# CPU_STM32H7.net
KiCad netlist of a schematic drawn in Altium Designer
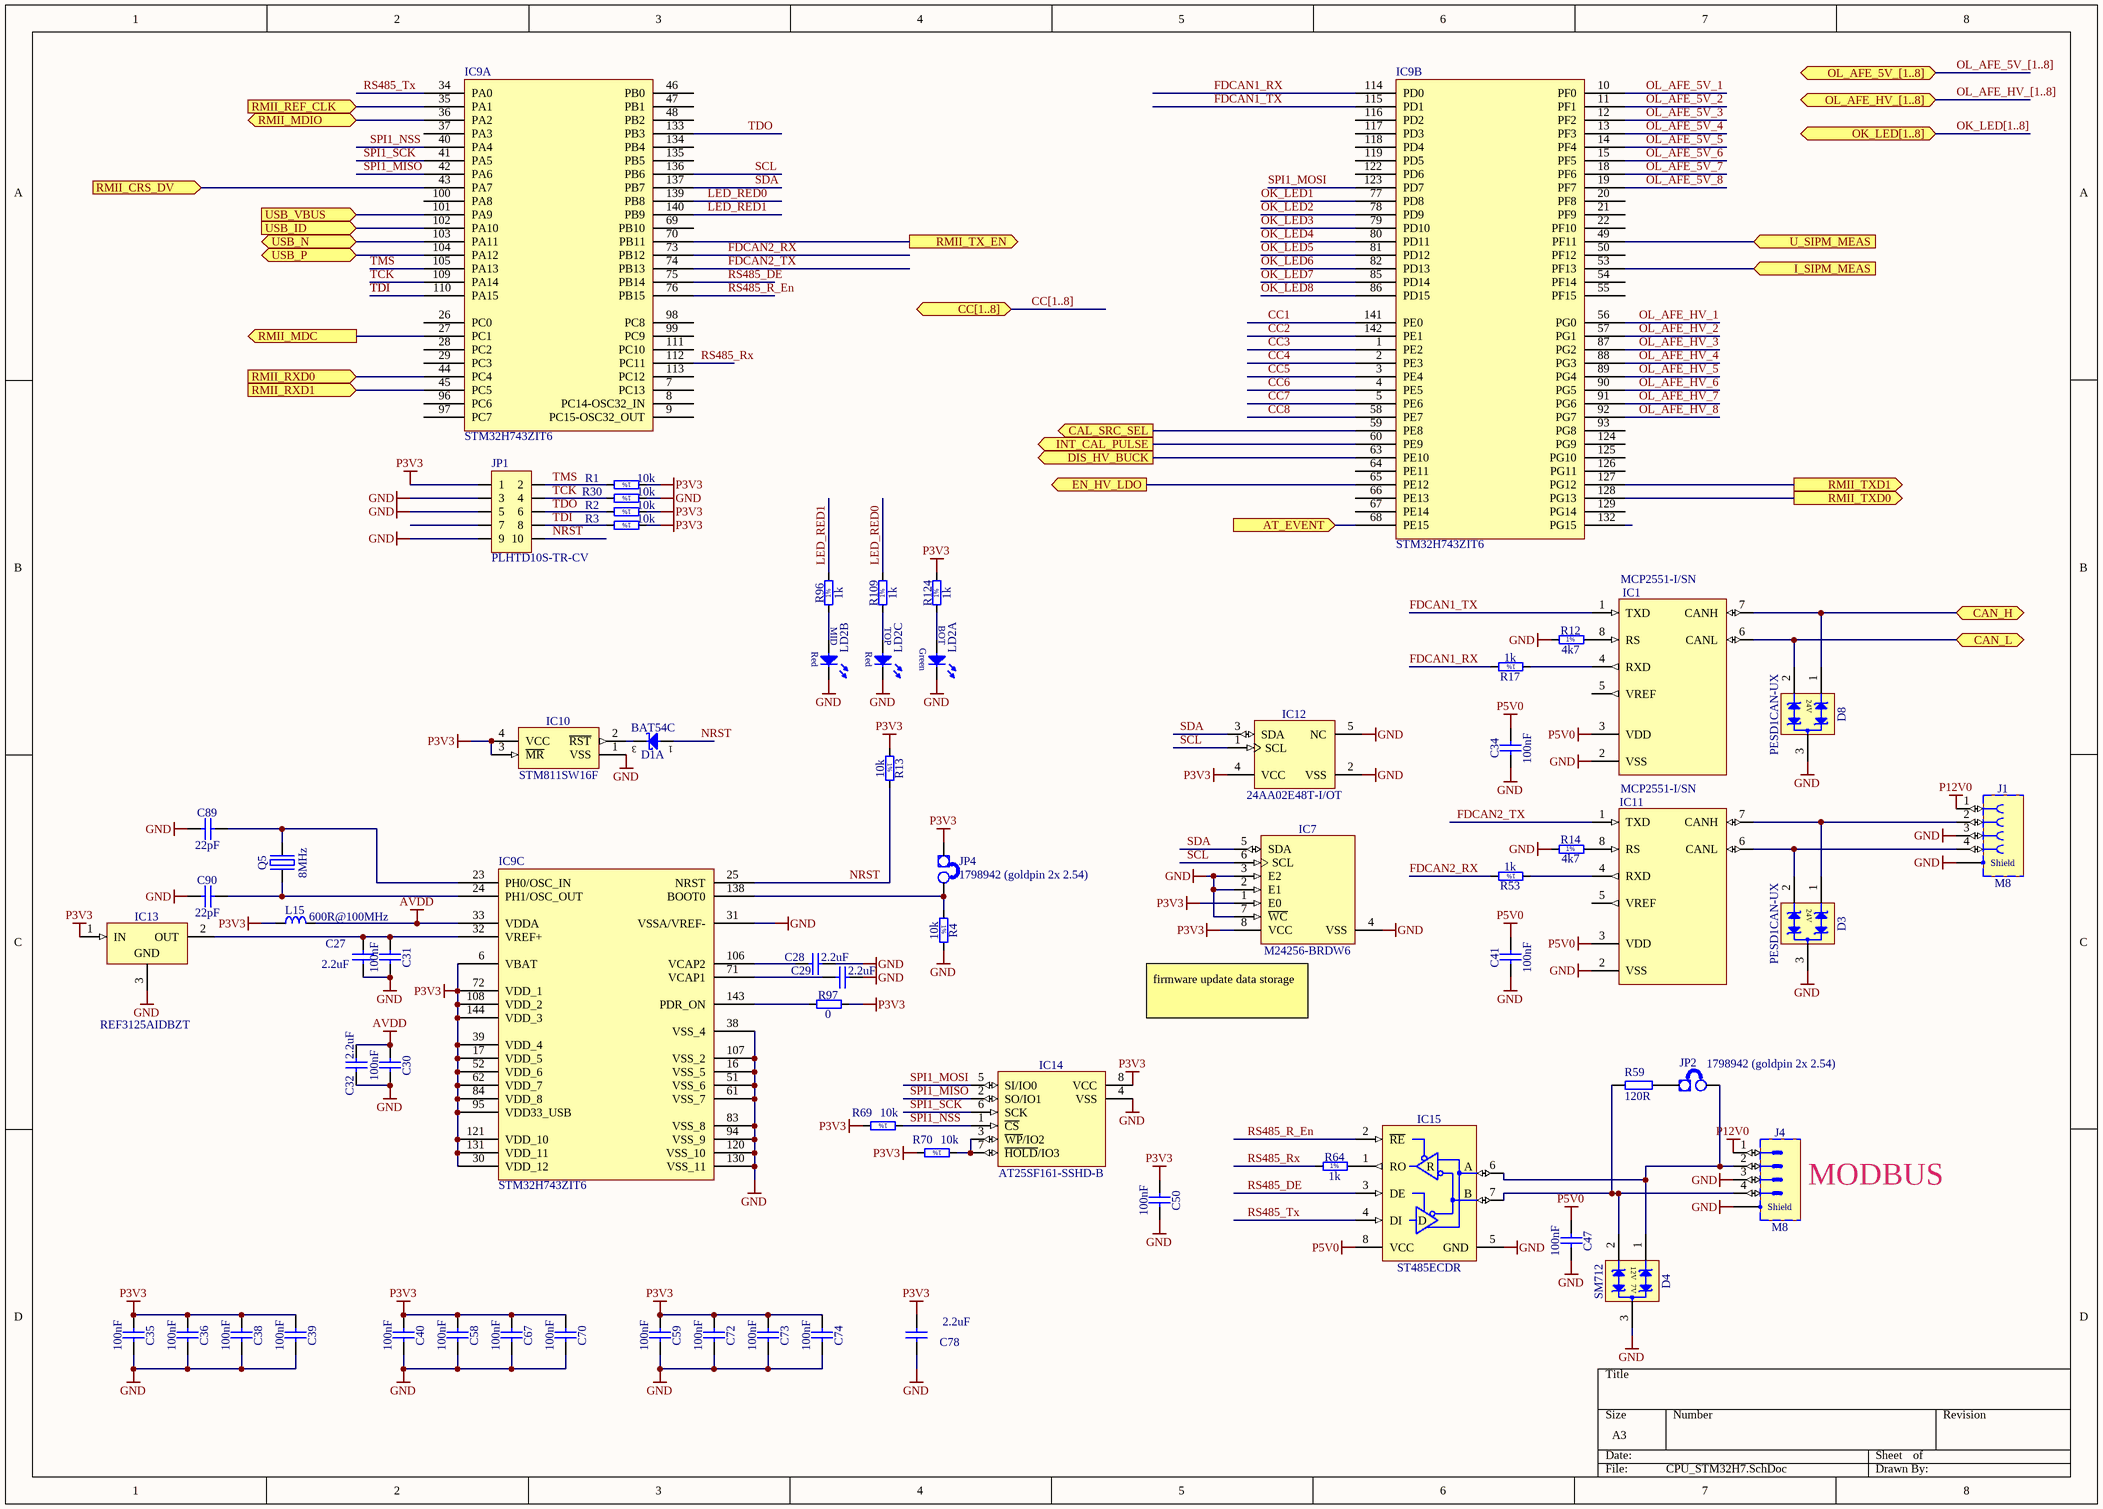
[diagram p0: CPU_STM32H7.SchDoc]

(export (version "E")
  (design (tool "Eeschema 10.0.6"))
  (components
    (comp (ref "C27")
      (value "2.2uF")
      (footprint "CAPC1608X90N")
      (description "Non-polarised capacitor")
      (fields (field (name "PART NUMBER") "CC0603_2.2UF_10V_20%_X7R") (field (name "VOLTAGE") "10V"))
      (libsource (lib "Capacitors") (part "Capacitor - non polarized"))
    )
    (comp (ref "C28")
      (value "2.2uF")
      (footprint "CAPC1608X90N")
      (description "Non-polarised capacitor")
      (fields (field (name "PART NUMBER") "CC0603_2.2UF_10V_20%_X7R") (field (name "VOLTAGE") "10V"))
      (libsource (lib "Capacitors") (part "Capacitor - non polarized"))
    )
    (comp (ref "C29")
      (value "2.2uF")
      (footprint "CAPC1608X90N")
      (description "Non-polarised capacitor")
      (fields (field (name "PART NUMBER") "CC0603_2.2UF_10V_20%_X7R") (field (name "VOLTAGE") "10V"))
      (libsource (lib "Capacitors") (part "Capacitor - non polarized"))
    )
    (comp (ref "C30")
      (value "100nF")
      (footprint "CAPC1005X55N")
      (description "Non-polarised capacitor")
      (fields (field (name "PART NUMBER") "CC0402_100NF_16V_10%_X7R") (field (name "VOLTAGE") "16V"))
      (libsource (lib "Capacitors") (part "Capacitor - non polarized"))
    )
    (comp (ref "C31")
      (value "100nF")
      (footprint "CAPC1005X55N")
      (description "Non-polarised capacitor")
      (fields (field (name "PART NUMBER") "CC0402_100NF_16V_10%_X7R") (field (name "VOLTAGE") "16V"))
      (libsource (lib "Capacitors") (part "Capacitor - non polarized"))
    )
    (comp (ref "C32")
      (value "2.2uF")
      (footprint "CAPC1608X90N")
      (description "Non-polarised capacitor")
      (fields (field (name "PART NUMBER") "CC0603_2.2UF_10V_20%_X7R") (field (name "VOLTAGE") "10V"))
      (libsource (lib "Capacitors") (part "Capacitor - non polarized"))
    )
    (comp (ref "C34")
      (value "100nF")
      (footprint "CAPC1005X55N")
      (description "Non-polarised capacitor")
      (fields (field (name "PART NUMBER") "CC0402_100NF_16V_10%_X7R") (field (name "VOLTAGE") "16V"))
      (libsource (lib "Capacitors") (part "Capacitor - non polarized"))
    )
    (comp (ref "C35")
      (value "100nF")
      (footprint "CAPC1005X55N")
      (description "Non-polarised capacitor")
      (fields (field (name "PART NUMBER") "CC0402_100NF_16V_10%_X7R") (field (name "VOLTAGE") "16V"))
      (libsource (lib "Capacitors") (part "Capacitor - non polarized"))
    )
    (comp (ref "C36")
      (value "100nF")
      (footprint "CAPC1005X55N")
      (description "Non-polarised capacitor")
      (fields (field (name "PART NUMBER") "CC0402_100NF_16V_10%_X7R") (field (name "VOLTAGE") "16V"))
      (libsource (lib "Capacitors") (part "Capacitor - non polarized"))
    )
    (comp (ref "C38")
      (value "100nF")
      (footprint "CAPC1005X55N")
      (description "Non-polarised capacitor")
      (fields (field (name "PART NUMBER") "CC0402_100NF_16V_10%_X7R") (field (name "VOLTAGE") "16V"))
      (libsource (lib "Capacitors") (part "Capacitor - non polarized"))
    )
    (comp (ref "C39")
      (value "100nF")
      (footprint "CAPC1005X55N")
      (description "Non-polarised capacitor")
      (fields (field (name "PART NUMBER") "CC0402_100NF_16V_10%_X7R") (field (name "VOLTAGE") "16V"))
      (libsource (lib "Capacitors") (part "Capacitor - non polarized"))
    )
    (comp (ref "C40")
      (value "100nF")
      (footprint "CAPC1005X55N")
      (description "Non-polarised capacitor")
      (fields (field (name "PART NUMBER") "CC0402_100NF_16V_10%_X7R") (field (name "VOLTAGE") "16V"))
      (libsource (lib "Capacitors") (part "Capacitor - non polarized"))
    )
    (comp (ref "C41")
      (value "100nF")
      (footprint "CAPC1005X55N")
      (description "Non-polarised capacitor")
      (fields (field (name "PART NUMBER") "CC0402_100NF_16V_10%_X7R") (field (name "VOLTAGE") "16V"))
      (libsource (lib "Capacitors") (part "Capacitor - non polarized"))
    )
    (comp (ref "C47")
      (value "100nF")
      (footprint "CAPC1005X55N")
      (description "Non-polarised capacitor")
      (fields (field (name "PART NUMBER") "CC0402_100NF_16V_10%_X7R") (field (name "VOLTAGE") "16V"))
      (libsource (lib "Capacitors") (part "Capacitor - non polarized"))
    )
    (comp (ref "C50")
      (value "100nF")
      (footprint "CAPC1005X55N")
      (description "Non-polarised capacitor")
      (fields (field (name "PART NUMBER") "CC0402_100NF_16V_10%_X7R") (field (name "VOLTAGE") "16V"))
      (libsource (lib "Capacitors") (part "Capacitor - non polarized"))
    )
    (comp (ref "C58")
      (value "100nF")
      (footprint "CAPC1005X55N")
      (description "Non-polarised capacitor")
      (fields (field (name "PART NUMBER") "CC0402_100NF_16V_10%_X7R") (field (name "VOLTAGE") "16V"))
      (libsource (lib "Capacitors") (part "Capacitor - non polarized"))
    )
    (comp (ref "C59")
      (value "100nF")
      (footprint "CAPC1005X55N")
      (description "Non-polarised capacitor")
      (fields (field (name "PART NUMBER") "CC0402_100NF_16V_10%_X7R") (field (name "VOLTAGE") "16V"))
      (libsource (lib "Capacitors") (part "Capacitor - non polarized"))
    )
    (comp (ref "C67")
      (value "100nF")
      (footprint "CAPC1005X55N")
      (description "Non-polarised capacitor")
      (fields (field (name "PART NUMBER") "CC0402_100NF_16V_10%_X7R") (field (name "VOLTAGE") "16V"))
      (libsource (lib "Capacitors") (part "Capacitor - non polarized"))
    )
    (comp (ref "C70")
      (value "100nF")
      (footprint "CAPC1005X55N")
      (description "Non-polarised capacitor")
      (fields (field (name "PART NUMBER") "CC0402_100NF_16V_10%_X7R") (field (name "VOLTAGE") "16V"))
      (libsource (lib "Capacitors") (part "Capacitor - non polarized"))
    )
    (comp (ref "C72")
      (value "100nF")
      (footprint "CAPC1005X55N")
      (description "Non-polarised capacitor")
      (fields (field (name "PART NUMBER") "CC0402_100NF_16V_10%_X7R") (field (name "VOLTAGE") "16V"))
      (libsource (lib "Capacitors") (part "Capacitor - non polarized"))
    )
    (comp (ref "C73")
      (value "100nF")
      (footprint "CAPC1005X55N")
      (description "Non-polarised capacitor")
      (fields (field (name "PART NUMBER") "CC0402_100NF_16V_10%_X7R") (field (name "VOLTAGE") "16V"))
      (libsource (lib "Capacitors") (part "Capacitor - non polarized"))
    )
    (comp (ref "C74")
      (value "100nF")
      (footprint "CAPC1005X55N")
      (description "Non-polarised capacitor")
      (fields (field (name "PART NUMBER") "CC0402_100NF_16V_10%_X7R") (field (name "VOLTAGE") "16V"))
      (libsource (lib "Capacitors") (part "Capacitor - non polarized"))
    )
    (comp (ref "C78")
      (value "2.2uF")
      (footprint "CAPC1608X90N")
      (description "Non-polarised capacitor")
      (fields (field (name "PART NUMBER") "CC0603_2.2UF_10V_20%_X7R") (field (name "VOLTAGE") "10V"))
      (libsource (lib "Capacitors") (part "Capacitor - non polarized"))
    )
    (comp (ref "C89")
      (value "22pF")
      (footprint "CAPC1005X55N")
      (description "Non-polarised capacitor")
      (fields (field (name "PART NUMBER") "CC0402_22PF_50V_5%_C0G") (field (name "VOLTAGE") "50V"))
      (libsource (lib "Capacitors") (part "Capacitor - non polarized"))
    )
    (comp (ref "C90")
      (value "22pF")
      (footprint "CAPC1005X55N")
      (description "Non-polarised capacitor")
      (fields (field (name "PART NUMBER") "CC0402_22PF_50V_5%_C0G") (field (name "VOLTAGE") "50V"))
      (libsource (lib "Capacitors") (part "Capacitor - non polarized"))
    )
    (comp (ref "D1")
      (value "BAT54C")
      (footprint "SOT95P240X130-3N")
      (description "Dual Common Cathode Schottky Diodes")
      (fields (field (name "VOLTAGE") "30V") (field (name "POWER") "200mA"))
      (libsource (lib "ICs And Semiconductors") (part "Diode Schottky x2 A1C3_A2C3"))
    )
    (comp (ref "D3")
      (value "PESD1CAN-UX")
      (footprint "SOT95P237X112-3N")
      (description "TVS Diode for CAN")
      (fields (field (name "VOLTAGE") "24V") (field (name "POWER") "400W"))
      (libsource (lib "LIBRARY_SCH") (part "D_TVS_PESD1CAN"))
    )
    (comp (ref "D4")
      (value "SM712")
      (footprint "SOT95P237X112-3N")
      (description "Asymmetrical TVS Diode for Extended Common-Mode RS-485")
      (fields (field (name "VOLTAGE") "12V/-7V") (field (name "POWER") "400W"))
      (libsource (lib "ICs And Semiconductors") (part "SM712"))
    )
    (comp (ref "D8")
      (value "PESD1CAN-UX")
      (footprint "SOT95P237X112-3N")
      (description "TVS Diode for CAN")
      (fields (field (name "VOLTAGE") "24V") (field (name "POWER") "400W"))
      (libsource (lib "LIBRARY_SCH") (part "D_TVS_PESD1CAN"))
    )
    (comp (ref "IC1")
      (value "MCP2551-I/SN")
      (footprint "SOIC127P600X175-8N")
      (description "High-Speed CAN Transceiver, 8-Pin SOIC, Industrial Temperature")
      (fields (field (name "MANUFACTURER") "MICROCHIP TECHNOLOGY"))
      (libsource (lib "LIBRARY_SCH") (part "IFC_MCP2551"))
    )
    (comp (ref "IC7")
      (value "M24256-BRDW6")
      (footprint "SOP65P640X120-8N")
      (description "256-Kbit Serial I²C Bus EEPROM")
      (fields
        (field (name "PART NUMBER") "M24256-BRDW6P")
        (field (name "MANUFACTURER") "ST MICROELECTRONICS")
      )
      (libsource (lib "LIBRARY_SCH") (part "MEM_M24256-BRDW6P"))
    )
    (comp (ref "IC9")
      (value "STM32H743ZIT6")
      (footprint "TSQFP50P2200X2200X160-144N")
      (description "32-bit Arm® Cortex-M7 400MHz MCUs, up to 2MB Flash,\r\n1MB RAM, 46 com. and analog interfaces")
      (libsource (lib "LIBRARY_SCH") (part "UPC_STM32H743ZIT6"))
    )
    (comp (ref "IC10")
      (value "STM811SW16F")
      (footprint "SOT143N")
      (description "Microprocessor Reset Circuit")
      (fields (field (name "MANUFACTURER") "ST MICROELECTRONICS"))
      (libsource (lib "ICs And Semiconductors") (part "STM811"))
    )
    (comp (ref "IC11")
      (value "MCP2551-I/SN")
      (footprint "SOIC127P600X175-8N")
      (description "High-Speed CAN Transceiver, 8-Pin SOIC, Industrial Temperature")
      (fields (field (name "MANUFACTURER") "MICROCHIP TECHNOLOGY"))
      (libsource (lib "LIBRARY_SCH") (part "IFC_MCP2551"))
    )
    (comp (ref "IC12")
      (value "24AA02E48T-I/OT")
      (footprint "SOT95P280X145-5N")
      (description "1.7V-5.5V, 2K I2C Serial EEPROM With EUI-48 Node Identity")
      (fields (field (name "MANUFACTURER") "MICROCHIP TECHNOLOGY"))
      (libsource (lib "ICs And Semiconductors") (part "24AA02E48T-I/OT"))
    )
    (comp (ref "IC13")
      (value "REF3125AIDBZT")
      (footprint "SOT95P237X112-3N")
      (description "3-Terminal Regulator 1=IN 2=OUT 3=GND")
      (fields (field (name "MANUFACTURER") "TEXAS INSTRUMENTS"))
      (libsource (lib "ICs And Semiconductors") (part "REG3 1IN-2OUT-3GND"))
    )
    (comp (ref "IC14")
      (value "AT25SF161-SSHD-B")
      (footprint "SOIC127P790X216-8N")
      (description "16Mb, 3V, Multiple I/O Serial NOR Flash Memory")
      (libsource (lib "LIBRARY_SCH") (part "MEM_AT25SF161"))
    )
    (comp (ref "IC15")
      (value "ST485ECDR")
      (footprint "SOIC127P600X175-8N")
      (description "±15kV ESD-Protected, Low Power  RS-485/RS-422 Transceiver")
      (fields (field (name "MANUFACTURER") "ST MICROELECTRONICS"))
      (libsource (lib "ICs And Semiconductors") (part "ST485EC"))
    )
    (comp (ref "J1")
      (value "M8")
      (footprint "AMPHENOL_M8AS-04PFFR-SF8001")
      (description "Connector 4 Female + Shield")
      (fields
        (field (name "PART NUMBER") "AMPHENOL_M8AS-04PFFR-SF8001")
        (field (name "MANUFACTURER") "AMPHENOL")
      )
      (libsource (lib "Connectors") (part "Connector 4 Female + Shield"))
    )
    (comp (ref "J4")
      (value "M8")
      (footprint "AMPHENOL_M8AS-04PMMR-SF8001")
      (description "Connector 4 Male + Shield")
      (fields
        (field (name "PART NUMBER") "AMPHENOL_M8AS-04PMMR-SF8001")
        (field (name "MANUFACTURER") "AMPHENOL")
      )
      (libsource (lib "Connectors") (part "Connector 4 Male + Shield"))
    )
    (comp (ref "JP1")
      (value "PLHTD10S-TR-CV")
      (footprint "PLHTD10S-TR-CV")
      (description "1.27 mm dual row goldpin (Maritex)")
      (libsource (lib "LIBRARY_SCH") (part "CON_2x5 1.27 SMT Male"))
    )
    (comp (ref "JP2")
      (value "1798942 (goldpin 2x 2.54)")
      (footprint "jump")
      (description "Jumper")
      (libsource (lib "") (part "JUMPER_1"))
    )
    (comp (ref "JP4")
      (value "1798942 (goldpin 2x 2.54)")
      (footprint "jump")
      (description "Jumper")
      (libsource (lib "LIBRARY_SCH") (part "JUMPER"))
    )
    (comp (ref "L15")
      (value "600R@100MHz")
      (footprint "INDC1005X55N")
      (description "Inductor")
      (fields (field (name "PART NUMBER") "IND0402_MURATA_BLM15HD601SN1") (field (name "POWER") "300mA"))
      (libsource (lib "Inductors & Transformers") (part "Inductor"))
    )
    (comp (ref "LD2")
      (value "Red/Red/Green")
      (footprint "LED_DIALIGHT_570-0100-112F")
      (description "LED x3  Top Red, Middle Red, Bottom Green")
      (fields
        (field (name "PART NUMBER") "LED_DIALIGHT_570-0100-112F")
        (field (name "MANUFACTURER") "DIALIGHT")
      )
      (libsource (lib "ICs And Semiconductors") (part "LED x3 G-1C2A-BOT_R-3C4A_R-5C6A-TOP"))
    )
    (comp (ref "Q5")
      (value "8MHz")
      (footprint "XTAL_TXC_7A")
      (description "Quartz Crystal")
      (fields
        (field (name "PART NUMBER") "XTAL_8MHZ_TXC_7A-8.000MAAE-T")
        (field (name "MANUFACTURER") "TXC CORPORATION")
      )
      (libsource (lib "ICs And Semiconductors") (part "Quartz Crystal"))
    )
    (comp (ref "R1")
      (value "10k")
      (footprint "RESC1005X40N")
      (description "Resistor - 1%")
      (fields (field (name "PART NUMBER") "R0402_10K_1%_0.0625W_100PPM") (field (name "POWER") "0.0625W"))
      (libsource (lib "Resistors") (part "Resistor - 1%"))
    )
    (comp (ref "R2")
      (value "10k")
      (footprint "RESC1005X40N")
      (description "Resistor - 1%")
      (fields (field (name "PART NUMBER") "R0402_10K_1%_0.0625W_100PPM") (field (name "POWER") "0.0625W"))
      (libsource (lib "Resistors") (part "Resistor - 1%"))
    )
    (comp (ref "R3")
      (value "10k")
      (footprint "RESC1005X40N")
      (description "Resistor - 1%")
      (fields (field (name "PART NUMBER") "R0402_10K_1%_0.0625W_100PPM") (field (name "POWER") "0.0625W"))
      (libsource (lib "Resistors") (part "Resistor - 1%"))
    )
    (comp (ref "R4")
      (value "10k")
      (footprint "RESC1005X40N")
      (description "Resistor - 1%")
      (fields (field (name "PART NUMBER") "R0402_10K_1%_0.0625W_100PPM") (field (name "POWER") "0.0625W"))
      (libsource (lib "Resistors") (part "Resistor - 1%"))
    )
    (comp (ref "R12")
      (value "4k7")
      (footprint "RESC1005X40N")
      (description "Resistor - 1%")
      (fields (field (name "PART NUMBER") "R0402_4K7_1%_0.0625W_100PPM") (field (name "POWER") "0.0625W"))
      (libsource (lib "Resistors") (part "Resistor - 1%"))
    )
    (comp (ref "R13")
      (value "10k")
      (footprint "RESC1005X40N")
      (description "Resistor - 1%")
      (fields (field (name "PART NUMBER") "R0402_10K_1%_0.0625W_100PPM") (field (name "POWER") "0.0625W"))
      (libsource (lib "Resistors") (part "Resistor - 1%"))
    )
    (comp (ref "R14")
      (value "4k7")
      (footprint "RESC1005X40N")
      (description "Resistor - 1%")
      (fields (field (name "PART NUMBER") "R0402_4K7_1%_0.0625W_100PPM") (field (name "POWER") "0.0625W"))
      (libsource (lib "Resistors") (part "Resistor - 1%"))
    )
    (comp (ref "R17")
      (value "1k")
      (footprint "RESC1005X40N")
      (description "Resistor - 1%")
      (fields (field (name "PART NUMBER") "R0402_1K_1%_0.0625W_100PPM") (field (name "POWER") "0.0625W"))
      (libsource (lib "Resistors") (part "Resistor - 1%"))
    )
    (comp (ref "R30")
      (value "10k")
      (footprint "RESC1005X40N")
      (description "Resistor - 1%")
      (fields (field (name "PART NUMBER") "R0402_10K_1%_0.0625W_100PPM") (field (name "POWER") "0.0625W"))
      (libsource (lib "Resistors") (part "Resistor - 1%"))
    )
    (comp (ref "R53")
      (value "1k")
      (footprint "RESC1005X40N")
      (description "Resistor - 1%")
      (fields (field (name "PART NUMBER") "R0402_1K_1%_0.0625W_100PPM") (field (name "POWER") "0.0625W"))
      (libsource (lib "Resistors") (part "Resistor - 1%"))
    )
    (comp (ref "R59")
      (value "120R")
      (footprint "1206R")
      (description "SMD Resistor")
      (libsource (lib "LIBRARY_SCH") (part "RES_1206"))
    )
    (comp (ref "R64")
      (value "1k")
      (footprint "RESC1005X40N")
      (description "Resistor - 1%")
      (fields (field (name "PART NUMBER") "R0402_1K_1%_0.0625W_100PPM") (field (name "POWER") "0.0625W"))
      (libsource (lib "Resistors") (part "Resistor - 1%"))
    )
    (comp (ref "R69")
      (value "10k")
      (footprint "RESC1005X40N")
      (description "Resistor - 1%")
      (fields (field (name "PART NUMBER") "R0402_10K_1%_0.0625W_100PPM") (field (name "POWER") "0.0625W"))
      (libsource (lib "Resistors") (part "Resistor - 1%"))
    )
    (comp (ref "R70")
      (value "10k")
      (footprint "RESC1005X40N")
      (description "Resistor - 1%")
      (fields (field (name "PART NUMBER") "R0402_10K_1%_0.0625W_100PPM") (field (name "POWER") "0.0625W"))
      (libsource (lib "Resistors") (part "Resistor - 1%"))
    )
    (comp (ref "R96")
      (value "1k")
      (footprint "RESC1005X40N")
      (description "Resistor - 1%")
      (fields (field (name "PART NUMBER") "R0402_1K_1%_0.0625W_100PPM") (field (name "POWER") "0.0625W"))
      (libsource (lib "Resistors") (part "Resistor - 1%"))
    )
    (comp (ref "R97")
      (value "0")
      (footprint "RESC1608X55N")
      (description "Resistor")
      (fields (field (name "PART NUMBER") "R0603_0R_JUMPER") (field (name "MANUFACTURER") "GENERIC"))
      (libsource (lib "Resistors") (part "Resistor"))
    )
    (comp (ref "R109")
      (value "1k")
      (footprint "RESC1005X40N")
      (description "Resistor - 1%")
      (fields (field (name "PART NUMBER") "R0402_1K_1%_0.0625W_100PPM") (field (name "POWER") "0.0625W"))
      (libsource (lib "Resistors") (part "Resistor - 1%"))
    )
    (comp (ref "R124")
      (value "1k")
      (footprint "RESC1005X40N")
      (description "Resistor - 1%")
      (fields (field (name "PART NUMBER") "R0402_1K_1%_0.0625W_100PPM") (field (name "POWER") "0.0625W"))
      (libsource (lib "Resistors") (part "Resistor - 1%"))
    )
  )
  (nets
    (net (code "1") (name "/AT_EVENT") (class "Default")
      (node (ref "IC9") (pin "68") (pinfunction "PE15_68") (pintype "passive"))
    )
    (net (code "2") (name "/CAL_SRC_SEL") (class "Default")
      (node (ref "IC9") (pin "59") (pinfunction "PE8_59") (pintype "passive"))
    )
    (net (code "3") (name "/CAN_H") (class "Default")
      (node (ref "D8") (pin "1") (pinfunction "I/O1_1") (pintype "passive"))
      (node (ref "IC1") (pin "7") (pinfunction "CANH_7") (pintype "bidirectional"))
    )
    (net (code "4") (name "/CAN_L") (class "Default")
      (node (ref "D8") (pin "2") (pinfunction "I/O2_2") (pintype "passive"))
      (node (ref "IC1") (pin "6") (pinfunction "CANL_6") (pintype "bidirectional"))
    )
    (net (code "5") (name "/CC1") (class "Default")
      (node (ref "IC9") (pin "141") (pinfunction "PE0_141") (pintype "passive"))
    )
    (net (code "6") (name "/CC2") (class "Default")
      (node (ref "IC9") (pin "142") (pinfunction "PE1_142") (pintype "passive"))
    )
    (net (code "7") (name "/CC3") (class "Default")
      (node (ref "IC9") (pin "1") (pinfunction "PE2_1") (pintype "passive"))
    )
    (net (code "8") (name "/CC4") (class "Default")
      (node (ref "IC9") (pin "2") (pinfunction "PE3_2") (pintype "passive"))
    )
    (net (code "9") (name "/CC5") (class "Default")
      (node (ref "IC9") (pin "3") (pinfunction "PE4_3") (pintype "passive"))
    )
    (net (code "10") (name "/CC6") (class "Default")
      (node (ref "IC9") (pin "4") (pinfunction "PE5_4") (pintype "passive"))
    )
    (net (code "11") (name "/CC7") (class "Default")
      (node (ref "IC9") (pin "5") (pinfunction "PE6_5") (pintype "passive"))
    )
    (net (code "12") (name "/CC8") (class "Default")
      (node (ref "IC9") (pin "58") (pinfunction "PE7_58") (pintype "passive"))
    )
    (net (code "14") (name "/DIS_HV_BUCK") (class "Default")
      (node (ref "IC9") (pin "63") (pinfunction "PE10_63") (pintype "passive"))
    )
    (net (code "15") (name "/EN_HV_LDO") (class "Default")
      (node (ref "IC9") (pin "65") (pinfunction "PE12_65") (pintype "passive"))
    )
    (net (code "16") (name "/FDCAN1_RX") (class "Default")
      (node (ref "IC9") (pin "114") (pinfunction "PD0_114") (pintype "passive"))
      (node (ref "R17") (pin "2") (pinfunction "2_2") (pintype "passive"))
    )
    (net (code "17") (name "/FDCAN1_TX") (class "Default")
      (node (ref "IC1") (pin "1") (pinfunction "TXD_1") (pintype "input"))
      (node (ref "IC9") (pin "115") (pinfunction "PD1_115") (pintype "passive"))
    )
    (net (code "18") (name "/FDCAN2_RX") (class "Default")
      (node (ref "IC9") (pin "73") (pinfunction "PB12_73") (pintype "passive"))
      (node (ref "R53") (pin "2") (pinfunction "2_2") (pintype "passive"))
    )
    (net (code "19") (name "/FDCAN2_TX") (class "Default")
      (node (ref "IC11") (pin "1") (pinfunction "TXD_1") (pintype "input"))
      (node (ref "IC9") (pin "74") (pinfunction "PB13_74") (pintype "passive"))
    )
    (net (code "20") (name "/INT_CAL_PULSE") (class "Default")
      (node (ref "IC9") (pin "60") (pinfunction "PE9_60") (pintype "passive"))
    )
    (net (code "21") (name "/I_SIPM_MEAS") (class "Default")
      (node (ref "IC9") (pin "53") (pinfunction "PF13_53") (pintype "passive"))
    )
    (net (code "22") (name "/LED_RED0") (class "Default")
      (node (ref "IC9") (pin "139") (pinfunction "PB8_139") (pintype "passive"))
      (node (ref "R109") (pin "2") (pinfunction "2_2") (pintype "passive"))
    )
    (net (code "23") (name "/LED_RED1") (class "Default")
      (node (ref "IC9") (pin "140") (pinfunction "PB9_140") (pintype "passive"))
      (node (ref "R96") (pin "2") (pinfunction "2_2") (pintype "passive"))
    )
    (net (code "24") (name "/NRST") (class "Default")
      (node (ref "D1") (pin "1") (pinfunction "A_1") (pintype "passive"))
      (node (ref "IC9") (pin "25") (pinfunction "NRST_25") (pintype "passive"))
      (node (ref "JP1") (pin "10") (pinfunction "10_10") (pintype "passive"))
      (node (ref "R13") (pin "2") (pinfunction "2_2") (pintype "passive"))
    )
    (net (code "25") (name "/OK_LED1") (class "Default")
      (node (ref "IC9") (pin "77") (pinfunction "PD8_77") (pintype "passive"))
    )
    (net (code "26") (name "/OK_LED2") (class "Default")
      (node (ref "IC9") (pin "78") (pinfunction "PD9_78") (pintype "passive"))
    )
    (net (code "27") (name "/OK_LED3") (class "Default")
      (node (ref "IC9") (pin "79") (pinfunction "PD10_79") (pintype "passive"))
    )
    (net (code "28") (name "/OK_LED4") (class "Default")
      (node (ref "IC9") (pin "80") (pinfunction "PD11_80") (pintype "passive"))
    )
    (net (code "29") (name "/OK_LED5") (class "Default")
      (node (ref "IC9") (pin "81") (pinfunction "PD12_81") (pintype "passive"))
    )
    (net (code "30") (name "/OK_LED6") (class "Default")
      (node (ref "IC9") (pin "82") (pinfunction "PD13_82") (pintype "passive"))
    )
    (net (code "31") (name "/OK_LED7") (class "Default")
      (node (ref "IC9") (pin "85") (pinfunction "PD14_85") (pintype "passive"))
    )
    (net (code "32") (name "/OK_LED8") (class "Default")
      (node (ref "IC9") (pin "86") (pinfunction "PD15_86") (pintype "passive"))
    )
    (net (code "34") (name "/OL_AFE_5V_1") (class "Default")
      (node (ref "IC9") (pin "10") (pinfunction "PF0_10") (pintype "passive"))
    )
    (net (code "35") (name "/OL_AFE_5V_2") (class "Default")
      (node (ref "IC9") (pin "11") (pinfunction "PF1_11") (pintype "passive"))
    )
    (net (code "36") (name "/OL_AFE_5V_3") (class "Default")
      (node (ref "IC9") (pin "12") (pinfunction "PF2_12") (pintype "passive"))
    )
    (net (code "37") (name "/OL_AFE_5V_4") (class "Default")
      (node (ref "IC9") (pin "13") (pinfunction "PF3_13") (pintype "passive"))
    )
    (net (code "38") (name "/OL_AFE_5V_5") (class "Default")
      (node (ref "IC9") (pin "14") (pinfunction "PF4_14") (pintype "passive"))
    )
    (net (code "39") (name "/OL_AFE_5V_6") (class "Default")
      (node (ref "IC9") (pin "15") (pinfunction "PF5_15") (pintype "passive"))
    )
    (net (code "40") (name "/OL_AFE_5V_7") (class "Default")
      (node (ref "IC9") (pin "18") (pinfunction "PF6_18") (pintype "passive"))
    )
    (net (code "41") (name "/OL_AFE_5V_8") (class "Default")
      (node (ref "IC9") (pin "19") (pinfunction "PF7_19") (pintype "passive"))
    )
    (net (code "43") (name "/OL_AFE_HV_1") (class "Default")
      (node (ref "IC9") (pin "56") (pinfunction "PG0_56") (pintype "passive"))
    )
    (net (code "44") (name "/OL_AFE_HV_2") (class "Default")
      (node (ref "IC9") (pin "57") (pinfunction "PG1_57") (pintype "passive"))
    )
    (net (code "45") (name "/OL_AFE_HV_3") (class "Default")
      (node (ref "IC9") (pin "87") (pinfunction "PG2_87") (pintype "passive"))
    )
    (net (code "46") (name "/OL_AFE_HV_4") (class "Default")
      (node (ref "IC9") (pin "88") (pinfunction "PG3_88") (pintype "passive"))
    )
    (net (code "47") (name "/OL_AFE_HV_5") (class "Default")
      (node (ref "IC9") (pin "89") (pinfunction "PG4_89") (pintype "passive"))
    )
    (net (code "48") (name "/OL_AFE_HV_6") (class "Default")
      (node (ref "IC9") (pin "90") (pinfunction "PG5_90") (pintype "passive"))
    )
    (net (code "49") (name "/OL_AFE_HV_7") (class "Default")
      (node (ref "IC9") (pin "91") (pinfunction "PG6_91") (pintype "passive"))
    )
    (net (code "50") (name "/OL_AFE_HV_8") (class "Default")
      (node (ref "IC9") (pin "92") (pinfunction "PG7_92") (pintype "passive"))
    )
    (net (code "52") (name "/RMII_CRS_DV") (class "Default")
      (node (ref "IC9") (pin "43") (pinfunction "PA7_43") (pintype "passive"))
    )
    (net (code "53") (name "/RMII_MDC") (class "Default")
      (node (ref "IC9") (pin "27") (pinfunction "PC1_27") (pintype "passive"))
    )
    (net (code "54") (name "/RMII_MDIO") (class "Default")
      (node (ref "IC9") (pin "36") (pinfunction "PA2_36") (pintype "passive"))
    )
    (net (code "55") (name "/RMII_REF_CLK") (class "Default")
      (node (ref "IC9") (pin "35") (pinfunction "PA1_35") (pintype "passive"))
    )
    (net (code "56") (name "/RMII_RXD0") (class "Default")
      (node (ref "IC9") (pin "44") (pinfunction "PC4_44") (pintype "passive"))
    )
    (net (code "57") (name "/RMII_RXD1") (class "Default")
      (node (ref "IC9") (pin "45") (pinfunction "PC5_45") (pintype "passive"))
    )
    (net (code "58") (name "/RMII_TXD0") (class "Default")
      (node (ref "IC9") (pin "128") (pinfunction "PG13_128") (pintype "passive"))
    )
    (net (code "59") (name "/RMII_TXD1") (class "Default")
      (node (ref "IC9") (pin "127") (pinfunction "PG12_127") (pintype "passive"))
    )
    (net (code "60") (name "/RMII_TX_EN") (class "Default")
      (node (ref "IC9") (pin "70") (pinfunction "PB11_70") (pintype "passive"))
    )
    (net (code "61") (name "/RS485_DE") (class "Default")
      (node (ref "IC15") (pin "3") (pinfunction "DE_3") (pintype "input"))
      (node (ref "IC9") (pin "75") (pinfunction "PB14_75") (pintype "passive"))
    )
    (net (code "62") (name "/RS485_R_En") (class "Default")
      (node (ref "IC15") (pin "2") (pinfunction "~{RE}_2") (pintype "input"))
      (node (ref "IC9") (pin "76") (pinfunction "PB15_76") (pintype "passive"))
    )
    (net (code "63") (name "/RS485_Rx") (class "Default")
      (node (ref "IC9") (pin "112") (pinfunction "PC11_112") (pintype "passive"))
      (node (ref "R64") (pin "1") (pinfunction "1_1") (pintype "passive"))
    )
    (net (code "64") (name "/RS485_Tx") (class "Default")
      (node (ref "IC15") (pin "4") (pinfunction "DI_4") (pintype "input"))
      (node (ref "IC9") (pin "34") (pinfunction "PA0_34") (pintype "passive"))
    )
    (net (code "65") (name "/SCL") (class "Default")
      (node (ref "IC12") (pin "1") (pinfunction "SCL_1") (pintype "input"))
      (node (ref "IC7") (pin "6") (pinfunction "SCL_6") (pintype "input"))
      (node (ref "IC9") (pin "136") (pinfunction "PB6_136") (pintype "passive"))
    )
    (net (code "66") (name "/SDA") (class "Default")
      (node (ref "IC12") (pin "3") (pinfunction "SDA_3") (pintype "bidirectional"))
      (node (ref "IC7") (pin "5") (pinfunction "SDA_5") (pintype "bidirectional"))
      (node (ref "IC9") (pin "137") (pinfunction "PB7_137") (pintype "passive"))
    )
    (net (code "67") (name "/SPI1_MISO") (class "Default")
      (node (ref "IC14") (pin "2") (pinfunction "SO/IO1_2") (pintype "bidirectional"))
      (node (ref "IC9") (pin "42") (pinfunction "PA6_42") (pintype "passive"))
    )
    (net (code "68") (name "/SPI1_MOSI") (class "Default")
      (node (ref "IC14") (pin "5") (pinfunction "SI/IO0_5") (pintype "bidirectional"))
      (node (ref "IC9") (pin "123") (pinfunction "PD7_123") (pintype "passive"))
    )
    (net (code "69") (name "/SPI1_NSS") (class "Default")
      (node (ref "IC14") (pin "1") (pinfunction "~{CS}_1") (pintype "input"))
      (node (ref "IC9") (pin "40") (pinfunction "PA4_40") (pintype "passive"))
      (node (ref "R69") (pin "1") (pinfunction "1_1") (pintype "passive"))
    )
    (net (code "70") (name "/SPI1_SCK") (class "Default")
      (node (ref "IC14") (pin "6") (pinfunction "SCK_6") (pintype "input"))
      (node (ref "IC9") (pin "41") (pinfunction "PA5_41") (pintype "passive"))
    )
    (net (code "71") (name "/TCK") (class "Default")
      (node (ref "IC9") (pin "109") (pinfunction "PA14_109") (pintype "passive"))
      (node (ref "JP1") (pin "4") (pinfunction "4_4") (pintype "passive"))
      (node (ref "R30") (pin "2") (pinfunction "2_2") (pintype "passive"))
    )
    (net (code "72") (name "/TDI") (class "Default")
      (node (ref "IC9") (pin "110") (pinfunction "PA15_110") (pintype "passive"))
      (node (ref "JP1") (pin "8") (pinfunction "8_8") (pintype "passive"))
      (node (ref "R3") (pin "2") (pinfunction "2_2") (pintype "passive"))
    )
    (net (code "73") (name "/TDO") (class "Default")
      (node (ref "IC9") (pin "133") (pinfunction "PB3_133") (pintype "passive"))
      (node (ref "JP1") (pin "6") (pinfunction "6_6") (pintype "passive"))
      (node (ref "R2") (pin "2") (pinfunction "2_2") (pintype "passive"))
    )
    (net (code "74") (name "/TMS") (class "Default")
      (node (ref "IC9") (pin "105") (pinfunction "PA13_105") (pintype "passive"))
      (node (ref "JP1") (pin "2") (pinfunction "2_2") (pintype "passive"))
      (node (ref "R1") (pin "2") (pinfunction "2_2") (pintype "passive"))
    )
    (net (code "75") (name "/USB_ID") (class "Default")
      (node (ref "IC9") (pin "102") (pinfunction "PA10_102") (pintype "passive"))
    )
    (net (code "76") (name "/USB_N") (class "Default")
      (node (ref "IC9") (pin "103") (pinfunction "PA11_103") (pintype "passive"))
    )
    (net (code "77") (name "/USB_P") (class "Default")
      (node (ref "IC9") (pin "104") (pinfunction "PA12_104") (pintype "passive"))
    )
    (net (code "78") (name "/USB_VBUS") (class "Default")
      (node (ref "IC9") (pin "101") (pinfunction "PA9_101") (pintype "passive"))
    )
    (net (code "79") (name "/U_SIPM_MEAS") (class "Default")
      (node (ref "IC9") (pin "49") (pinfunction "PF11_49") (pintype "passive"))
    )
    (net (code "80") (name "AVDD") (class "Default")
      (node (ref "C30") (pin "1") (pinfunction "1_1") (pintype "passive"))
      (node (ref "C32") (pin "2") (pinfunction "2_2") (pintype "passive"))
      (node (ref "IC9") (pin "33") (pinfunction "VDDA_33") (pintype "passive"))
      (node (ref "L15") (pin "2") (pinfunction "2_2") (pintype "passive"))
    )
    (net (code "81") (name "GND") (class "Default")
      (node (ref "C27") (pin "1") (pinfunction "1_1") (pintype "passive"))
      (node (ref "C28") (pin "2") (pinfunction "2_2") (pintype "passive"))
      (node (ref "C29") (pin "2") (pinfunction "2_2") (pintype "passive"))
      (node (ref "C30") (pin "2") (pinfunction "2_2") (pintype "passive"))
      (node (ref "C31") (pin "2") (pinfunction "2_2") (pintype "passive"))
      (node (ref "C32") (pin "1") (pinfunction "1_1") (pintype "passive"))
      (node (ref "C34") (pin "1") (pinfunction "1_1") (pintype "passive"))
      (node (ref "C35") (pin "2") (pinfunction "2_2") (pintype "passive"))
      (node (ref "C36") (pin "2") (pinfunction "2_2") (pintype "passive"))
      (node (ref "C38") (pin "2") (pinfunction "2_2") (pintype "passive"))
      (node (ref "C39") (pin "2") (pinfunction "2_2") (pintype "passive"))
      (node (ref "C40") (pin "2") (pinfunction "2_2") (pintype "passive"))
      (node (ref "C41") (pin "1") (pinfunction "1_1") (pintype "passive"))
      (node (ref "C47") (pin "2") (pinfunction "2_2") (pintype "passive"))
      (node (ref "C50") (pin "2") (pinfunction "2_2") (pintype "passive"))
      (node (ref "C58") (pin "2") (pinfunction "2_2") (pintype "passive"))
      (node (ref "C59") (pin "2") (pinfunction "2_2") (pintype "passive"))
      (node (ref "C67") (pin "2") (pinfunction "2_2") (pintype "passive"))
      (node (ref "C70") (pin "2") (pinfunction "2_2") (pintype "passive"))
      (node (ref "C72") (pin "2") (pinfunction "2_2") (pintype "passive"))
      (node (ref "C73") (pin "2") (pinfunction "2_2") (pintype "passive"))
      (node (ref "C74") (pin "2") (pinfunction "2_2") (pintype "passive"))
      (node (ref "C78") (pin "1") (pinfunction "1_1") (pintype "passive"))
      (node (ref "C89") (pin "1") (pinfunction "1_1") (pintype "passive"))
      (node (ref "C90") (pin "1") (pinfunction "1_1") (pintype "passive"))
      (node (ref "D3") (pin "3") (pinfunction "GND_3") (pintype "passive"))
      (node (ref "D4") (pin "3") (pinfunction "GND_3") (pintype "passive"))
      (node (ref "D8") (pin "3") (pinfunction "GND_3") (pintype "passive"))
      (node (ref "IC1") (pin "2") (pinfunction "VSS_2") (pintype "power_in"))
      (node (ref "IC10") (pin "1") (pinfunction "VSS_1") (pintype "power_in"))
      (node (ref "IC11") (pin "2") (pinfunction "VSS_2") (pintype "power_in"))
      (node (ref "IC12") (pin "2") (pinfunction "VSS_2") (pintype "power_in"))
      (node (ref "IC12") (pin "5") (pinfunction "NC_5") (pintype "passive"))
      (node (ref "IC13") (pin "3") (pinfunction "GND_3") (pintype "power_in"))
      (node (ref "IC14") (pin "4") (pinfunction "VSS_4") (pintype "power_in"))
      (node (ref "IC15") (pin "5") (pinfunction "GND_5") (pintype "power_in"))
      (node (ref "IC7") (pin "2") (pinfunction "E1_2") (pintype "input"))
      (node (ref "IC7") (pin "3") (pinfunction "E2_3") (pintype "input"))
      (node (ref "IC7") (pin "4") (pinfunction "VSS_4") (pintype "power_in"))
      (node (ref "IC7") (pin "7") (pinfunction "~{WC}_7") (pintype "input"))
      (node (ref "IC9") (pin "107") (pinfunction "VSS_2_107") (pintype "passive"))
      (node (ref "IC9") (pin "120") (pinfunction "VSS_10_120") (pintype "passive"))
      (node (ref "IC9") (pin "130") (pinfunction "VSS_11_130") (pintype "passive"))
      (node (ref "IC9") (pin "16") (pinfunction "VSS_5_16") (pintype "passive"))
      (node (ref "IC9") (pin "31") (pinfunction "VSSA/VREF-_31") (pintype "passive"))
      (node (ref "IC9") (pin "38") (pinfunction "VSS_4_38") (pintype "passive"))
      (node (ref "IC9") (pin "51") (pinfunction "VSS_6_51") (pintype "passive"))
      (node (ref "IC9") (pin "61") (pinfunction "VSS_7_61") (pintype "passive"))
      (node (ref "IC9") (pin "83") (pinfunction "VSS_8_83") (pintype "passive"))
      (node (ref "IC9") (pin "94") (pinfunction "VSS_9_94") (pintype "passive"))
      (node (ref "J1") (pin "3") (pinfunction "3_3") (pintype "bidirectional"))
      (node (ref "J1") (pin "SHIELD") (pinfunction "SHIELD_SHIELD") (pintype "passive"))
      (node (ref "J4") (pin "3") (pinfunction "3_3") (pintype "bidirectional"))
      (node (ref "J4") (pin "SHIELD") (pinfunction "SHIELD_SHIELD") (pintype "passive"))
      (node (ref "JP1") (pin "3") (pinfunction "3_3") (pintype "passive"))
      (node (ref "JP1") (pin "5") (pinfunction "5_5") (pintype "passive"))
      (node (ref "JP1") (pin "9") (pinfunction "9_9") (pintype "passive"))
      (node (ref "LD2") (pin "2") (pinfunction "C_2") (pintype "passive"))
      (node (ref "LD2") (pin "4") (pinfunction "C_4") (pintype "passive"))
      (node (ref "LD2") (pin "6") (pinfunction "C_6") (pintype "passive"))
      (node (ref "R12") (pin "1") (pinfunction "1_1") (pintype "passive"))
      (node (ref "R14") (pin "1") (pinfunction "1_1") (pintype "passive"))
      (node (ref "R30") (pin "1") (pinfunction "1_1") (pintype "passive"))
      (node (ref "R4") (pin "2") (pinfunction "2_2") (pintype "passive"))
    )
    (net (code "82") (name "Net-(D1A-COMC)") (class "Default")
      (node (ref "D1") (pin "3") (pinfunction "COMC_3") (pintype "passive"))
      (node (ref "IC10") (pin "2") (pinfunction "~{RST}_2") (pintype "output"))
    )
    (net (code "83") (name "Net-(D3-I{slash}O1)") (class "Default")
      (node (ref "D3") (pin "1") (pinfunction "I/O1_1") (pintype "passive"))
      (node (ref "IC11") (pin "7") (pinfunction "CANH_7") (pintype "bidirectional"))
      (node (ref "J1") (pin "2") (pinfunction "2_2") (pintype "bidirectional"))
    )
    (net (code "84") (name "Net-(D3-I{slash}O2)") (class "Default")
      (node (ref "D3") (pin "2") (pinfunction "I/O2_2") (pintype "passive"))
      (node (ref "IC11") (pin "6") (pinfunction "CANL_6") (pintype "bidirectional"))
      (node (ref "J1") (pin "4") (pinfunction "4_4") (pintype "bidirectional"))
    )
    (net (code "85") (name "Net-(D4-I{slash}O1)") (class "Default")
      (node (ref "D4") (pin "1") (pinfunction "I/O1_1") (pintype "passive"))
      (node (ref "IC15") (pin "6") (pinfunction "A_6") (pintype "bidirectional"))
      (node (ref "J4") (pin "2") (pinfunction "2_2") (pintype "bidirectional"))
      (node (ref "JP2") (pin "2") (pinfunction "E2_2") (pintype "passive"))
    )
    (net (code "86") (name "Net-(D4-I{slash}O2)") (class "Default")
      (node (ref "D4") (pin "2") (pinfunction "I/O2_2") (pintype "passive"))
      (node (ref "IC15") (pin "7") (pinfunction "B_7") (pintype "bidirectional"))
      (node (ref "J4") (pin "4") (pinfunction "4_4") (pintype "bidirectional"))
      (node (ref "R59") (pin "1") (pinfunction "1_1") (pintype "passive"))
    )
    (net (code "87") (name "Net-(IC1-RS)") (class "Default")
      (node (ref "IC1") (pin "8") (pinfunction "RS_8") (pintype "input"))
      (node (ref "R12") (pin "2") (pinfunction "2_2") (pintype "passive"))
    )
    (net (code "88") (name "Net-(IC1-RXD)") (class "Default")
      (node (ref "IC1") (pin "4") (pinfunction "RXD_4") (pintype "output"))
      (node (ref "R17") (pin "1") (pinfunction "1_1") (pintype "passive"))
    )
    (net (code "89") (name "Net-(IC9C-BOOT0)") (class "Default")
      (node (ref "IC9") (pin "138") (pinfunction "BOOT0_138") (pintype "passive"))
      (node (ref "JP4") (pin "2") (pinfunction "E2_2") (pintype "passive"))
      (node (ref "R4") (pin "1") (pinfunction "1_1") (pintype "passive"))
    )
    (net (code "90") (name "Net-(IC9C-PDR_ON)") (class "Default")
      (node (ref "IC9") (pin "143") (pinfunction "PDR_ON_143") (pintype "passive"))
      (node (ref "R97") (pin "1") (pinfunction "1_1") (pintype "passive"))
    )
    (net (code "91") (name "Net-(IC9C-PH0{slash}OSC_IN)") (class "Default")
      (node (ref "C89") (pin "2") (pinfunction "2_2") (pintype "passive"))
      (node (ref "IC9") (pin "23") (pinfunction "PH0/OSC_IN_23") (pintype "passive"))
      (node (ref "Q5") (pin "2") (pinfunction "OSC2_2") (pintype "passive"))
    )
    (net (code "92") (name "Net-(IC9C-PH1{slash}OSC_OUT)") (class "Default")
      (node (ref "C90") (pin "2") (pinfunction "2_2") (pintype "passive"))
      (node (ref "IC9") (pin "24") (pinfunction "PH1/OSC_OUT_24") (pintype "passive"))
      (node (ref "Q5") (pin "1") (pinfunction "OSC1_1") (pintype "passive"))
    )
    (net (code "93") (name "Net-(IC9C-VCAP1)") (class "Default")
      (node (ref "C29") (pin "1") (pinfunction "1_1") (pintype "passive"))
      (node (ref "IC9") (pin "71") (pinfunction "VCAP1_71") (pintype "passive"))
    )
    (net (code "94") (name "Net-(IC9C-VCAP2)") (class "Default")
      (node (ref "C28") (pin "1") (pinfunction "1_1") (pintype "passive"))
      (node (ref "IC9") (pin "106") (pinfunction "VCAP2_106") (pintype "passive"))
    )
    (net (code "95") (name "Net-(IC11-RS)") (class "Default")
      (node (ref "IC11") (pin "8") (pinfunction "RS_8") (pintype "input"))
      (node (ref "R14") (pin "2") (pinfunction "2_2") (pintype "passive"))
    )
    (net (code "96") (name "Net-(IC11-RXD)") (class "Default")
      (node (ref "IC11") (pin "4") (pinfunction "RXD_4") (pintype "output"))
      (node (ref "R53") (pin "1") (pinfunction "1_1") (pintype "passive"))
    )
    (net (code "97") (name "Net-(IC13-OUT)") (class "Default")
      (node (ref "C27") (pin "2") (pinfunction "2_2") (pintype "passive"))
      (node (ref "C31") (pin "1") (pinfunction "1_1") (pintype "passive"))
      (node (ref "IC13") (pin "2") (pinfunction "OUT_2") (pintype "power_in"))
      (node (ref "IC9") (pin "32") (pinfunction "VREF+_32") (pintype "passive"))
    )
    (net (code "98") (name "Net-(IC14-~{HOLD}{slash}IO3)") (class "Default")
      (node (ref "IC14") (pin "3") (pinfunction "~{WP}/IO2_3") (pintype "bidirectional"))
      (node (ref "IC14") (pin "7") (pinfunction "~{HOLD}/IO3_7") (pintype "bidirectional"))
      (node (ref "R70") (pin "1") (pinfunction "1_1") (pintype "passive"))
    )
    (net (code "99") (name "Net-(IC15-RO)") (class "Default")
      (node (ref "IC15") (pin "1") (pinfunction "RO_1") (pintype "output"))
      (node (ref "R64") (pin "2") (pinfunction "2_2") (pintype "passive"))
    )
    (net (code "100") (name "Net-(JP2-E1)") (class "Default")
      (node (ref "JP2") (pin "1") (pinfunction "E1_1") (pintype "passive"))
      (node (ref "R59") (pin "2") (pinfunction "2_2") (pintype "passive"))
    )
    (net (code "101") (name "Net-(LD2A-A)") (class "Default")
      (node (ref "LD2") (pin "1") (pinfunction "A_1") (pintype "passive"))
      (node (ref "R124") (pin "1") (pinfunction "1_1") (pintype "passive"))
    )
    (net (code "102") (name "Net-(LD2B-A)") (class "Default")
      (node (ref "LD2") (pin "3") (pinfunction "A_3") (pintype "passive"))
      (node (ref "R96") (pin "1") (pinfunction "1_1") (pintype "passive"))
    )
    (net (code "103") (name "Net-(LD2C-A)") (class "Default")
      (node (ref "LD2") (pin "5") (pinfunction "A_5") (pintype "passive"))
      (node (ref "R109") (pin "1") (pinfunction "1_1") (pintype "passive"))
    )
    (net (code "104") (name "P3V3") (class "Default")
      (node (ref "C35") (pin "1") (pinfunction "1_1") (pintype "passive"))
      (node (ref "C36") (pin "1") (pinfunction "1_1") (pintype "passive"))
      (node (ref "C38") (pin "1") (pinfunction "1_1") (pintype "passive"))
      (node (ref "C39") (pin "1") (pinfunction "1_1") (pintype "passive"))
      (node (ref "C40") (pin "1") (pinfunction "1_1") (pintype "passive"))
      (node (ref "C50") (pin "1") (pinfunction "1_1") (pintype "passive"))
      (node (ref "C58") (pin "1") (pinfunction "1_1") (pintype "passive"))
      (node (ref "C59") (pin "1") (pinfunction "1_1") (pintype "passive"))
      (node (ref "C67") (pin "1") (pinfunction "1_1") (pintype "passive"))
      (node (ref "C70") (pin "1") (pinfunction "1_1") (pintype "passive"))
      (node (ref "C72") (pin "1") (pinfunction "1_1") (pintype "passive"))
      (node (ref "C73") (pin "1") (pinfunction "1_1") (pintype "passive"))
      (node (ref "C74") (pin "1") (pinfunction "1_1") (pintype "passive"))
      (node (ref "C78") (pin "2") (pinfunction "2_2") (pintype "passive"))
      (node (ref "IC10") (pin "3") (pinfunction "~{MR}_3") (pintype "input"))
      (node (ref "IC10") (pin "4") (pinfunction "VCC_4") (pintype "power_in"))
      (node (ref "IC12") (pin "4") (pinfunction "VCC_4") (pintype "power_in"))
      (node (ref "IC13") (pin "1") (pinfunction "IN_1") (pintype "input"))
      (node (ref "IC14") (pin "8") (pinfunction "VCC_8") (pintype "power_in"))
      (node (ref "IC7") (pin "1") (pinfunction "E0_1") (pintype "input"))
      (node (ref "IC7") (pin "8") (pinfunction "VCC_8") (pintype "power_in"))
      (node (ref "IC9") (pin "108") (pinfunction "VDD_2_108") (pintype "passive"))
      (node (ref "IC9") (pin "121") (pinfunction "VDD_10_121") (pintype "passive"))
      (node (ref "IC9") (pin "131") (pinfunction "VDD_11_131") (pintype "passive"))
      (node (ref "IC9") (pin "144") (pinfunction "VDD_3_144") (pintype "passive"))
      (node (ref "IC9") (pin "17") (pinfunction "VDD_5_17") (pintype "passive"))
      (node (ref "IC9") (pin "30") (pinfunction "VDD_12_30") (pintype "passive"))
      (node (ref "IC9") (pin "39") (pinfunction "VDD_4_39") (pintype "passive"))
      (node (ref "IC9") (pin "52") (pinfunction "VDD_6_52") (pintype "passive"))
      (node (ref "IC9") (pin "6") (pinfunction "VBAT_6") (pintype "passive"))
      (node (ref "IC9") (pin "62") (pinfunction "VDD_7_62") (pintype "passive"))
      (node (ref "IC9") (pin "72") (pinfunction "VDD_1_72") (pintype "passive"))
      (node (ref "IC9") (pin "84") (pinfunction "VDD_8_84") (pintype "passive"))
      (node (ref "IC9") (pin "95") (pinfunction "VDD33_USB_95") (pintype "passive"))
      (node (ref "JP1") (pin "1") (pinfunction "1_1") (pintype "passive"))
      (node (ref "JP4") (pin "1") (pinfunction "E1_1") (pintype "passive"))
      (node (ref "L15") (pin "1") (pinfunction "1_1") (pintype "passive"))
      (node (ref "R1") (pin "1") (pinfunction "1_1") (pintype "passive"))
      (node (ref "R124") (pin "2") (pinfunction "2_2") (pintype "passive"))
      (node (ref "R13") (pin "1") (pinfunction "1_1") (pintype "passive"))
      (node (ref "R2") (pin "1") (pinfunction "1_1") (pintype "passive"))
      (node (ref "R3") (pin "1") (pinfunction "1_1") (pintype "passive"))
      (node (ref "R69") (pin "2") (pinfunction "2_2") (pintype "passive"))
      (node (ref "R70") (pin "2") (pinfunction "2_2") (pintype "passive"))
      (node (ref "R97") (pin "2") (pinfunction "2_2") (pintype "passive"))
    )
    (net (code "105") (name "P5V0") (class "Default")
      (node (ref "C34") (pin "2") (pinfunction "2_2") (pintype "passive"))
      (node (ref "C41") (pin "2") (pinfunction "2_2") (pintype "passive"))
      (node (ref "C47") (pin "1") (pinfunction "1_1") (pintype "passive"))
      (node (ref "IC1") (pin "3") (pinfunction "VDD_3") (pintype "power_in"))
      (node (ref "IC11") (pin "3") (pinfunction "VDD_3") (pintype "power_in"))
      (node (ref "IC15") (pin "8") (pinfunction "VCC_8") (pintype "power_in"))
    )
    (net (code "106") (name "P12V0") (class "Default")
      (node (ref "J1") (pin "1") (pinfunction "1_1") (pintype "bidirectional"))
      (node (ref "J4") (pin "1") (pinfunction "1_1") (pintype "bidirectional"))
    )
    (net (code "107") (name "unconnected-(IC1-VREF-Pad5)") (class "Default")
      (node (ref "IC1") (pin "5") (pinfunction "VREF_5") (pintype "output"))
    )
    (net (code "108") (name "unconnected-(IC9A-PA3-Pad37)") (class "Default")
      (node (ref "IC9") (pin "37") (pinfunction "PA3_37") (pintype "passive"))
    )
    (net (code "109") (name "unconnected-(IC9A-PA8-Pad100)") (class "Default")
      (node (ref "IC9") (pin "100") (pinfunction "PA8_100") (pintype "passive"))
    )
    (net (code "110") (name "unconnected-(IC9A-PB0-Pad46)") (class "Default")
      (node (ref "IC9") (pin "46") (pinfunction "PB0_46") (pintype "passive"))
    )
    (net (code "111") (name "unconnected-(IC9A-PB1-Pad47)") (class "Default")
      (node (ref "IC9") (pin "47") (pinfunction "PB1_47") (pintype "passive"))
    )
    (net (code "112") (name "unconnected-(IC9A-PB2-Pad48)") (class "Default")
      (node (ref "IC9") (pin "48") (pinfunction "PB2_48") (pintype "passive"))
    )
    (net (code "113") (name "unconnected-(IC9A-PB4-Pad134)") (class "Default")
      (node (ref "IC9") (pin "134") (pinfunction "PB4_134") (pintype "passive"))
    )
    (net (code "114") (name "unconnected-(IC9A-PB5-Pad135)") (class "Default")
      (node (ref "IC9") (pin "135") (pinfunction "PB5_135") (pintype "passive"))
    )
    (net (code "115") (name "unconnected-(IC9A-PB10-Pad69)") (class "Default")
      (node (ref "IC9") (pin "69") (pinfunction "PB10_69") (pintype "passive"))
    )
    (net (code "116") (name "unconnected-(IC9A-PC0-Pad26)") (class "Default")
      (node (ref "IC9") (pin "26") (pinfunction "PC0_26") (pintype "passive"))
    )
    (net (code "117") (name "unconnected-(IC9A-PC2-Pad28)") (class "Default")
      (node (ref "IC9") (pin "28") (pinfunction "PC2_28") (pintype "passive"))
    )
    (net (code "118") (name "unconnected-(IC9A-PC3-Pad29)") (class "Default")
      (node (ref "IC9") (pin "29") (pinfunction "PC3_29") (pintype "passive"))
    )
    (net (code "119") (name "unconnected-(IC9A-PC6-Pad96)") (class "Default")
      (node (ref "IC9") (pin "96") (pinfunction "PC6_96") (pintype "passive"))
    )
    (net (code "120") (name "unconnected-(IC9A-PC7-Pad97)") (class "Default")
      (node (ref "IC9") (pin "97") (pinfunction "PC7_97") (pintype "passive"))
    )
    (net (code "121") (name "unconnected-(IC9A-PC8-Pad98)") (class "Default")
      (node (ref "IC9") (pin "98") (pinfunction "PC8_98") (pintype "passive"))
    )
    (net (code "122") (name "unconnected-(IC9A-PC9-Pad99)") (class "Default")
      (node (ref "IC9") (pin "99") (pinfunction "PC9_99") (pintype "passive"))
    )
    (net (code "123") (name "unconnected-(IC9A-PC10-Pad111)") (class "Default")
      (node (ref "IC9") (pin "111") (pinfunction "PC10_111") (pintype "passive"))
    )
    (net (code "124") (name "unconnected-(IC9A-PC12-Pad113)") (class "Default")
      (node (ref "IC9") (pin "113") (pinfunction "PC12_113") (pintype "passive"))
    )
    (net (code "125") (name "unconnected-(IC9A-PC13-Pad7)") (class "Default")
      (node (ref "IC9") (pin "7") (pinfunction "PC13_7") (pintype "passive"))
    )
    (net (code "126") (name "unconnected-(IC9A-PC14-OSC32_IN-Pad8)") (class "Default")
      (node (ref "IC9") (pin "8") (pinfunction "PC14-OSC32_IN_8") (pintype "passive"))
    )
    (net (code "127") (name "unconnected-(IC9A-PC15-OSC32_OUT-Pad9)") (class "Default")
      (node (ref "IC9") (pin "9") (pinfunction "PC15-OSC32_OUT_9") (pintype "passive"))
    )
    (net (code "128") (name "unconnected-(IC9B-PD2-Pad116)") (class "Default")
      (node (ref "IC9") (pin "116") (pinfunction "PD2_116") (pintype "passive"))
    )
    (net (code "129") (name "unconnected-(IC9B-PD3-Pad117)") (class "Default")
      (node (ref "IC9") (pin "117") (pinfunction "PD3_117") (pintype "passive"))
    )
    (net (code "130") (name "unconnected-(IC9B-PD4-Pad118)") (class "Default")
      (node (ref "IC9") (pin "118") (pinfunction "PD4_118") (pintype "passive"))
    )
    (net (code "131") (name "unconnected-(IC9B-PD5-Pad119)") (class "Default")
      (node (ref "IC9") (pin "119") (pinfunction "PD5_119") (pintype "passive"))
    )
    (net (code "132") (name "unconnected-(IC9B-PD6-Pad122)") (class "Default")
      (node (ref "IC9") (pin "122") (pinfunction "PD6_122") (pintype "passive"))
    )
    (net (code "133") (name "unconnected-(IC9B-PE11-Pad64)") (class "Default")
      (node (ref "IC9") (pin "64") (pinfunction "PE11_64") (pintype "passive"))
    )
    (net (code "134") (name "unconnected-(IC9B-PE13-Pad66)") (class "Default")
      (node (ref "IC9") (pin "66") (pinfunction "PE13_66") (pintype "passive"))
    )
    (net (code "135") (name "unconnected-(IC9B-PE14-Pad67)") (class "Default")
      (node (ref "IC9") (pin "67") (pinfunction "PE14_67") (pintype "passive"))
    )
    (net (code "136") (name "unconnected-(IC9B-PF8-Pad20)") (class "Default")
      (node (ref "IC9") (pin "20") (pinfunction "PF8_20") (pintype "passive"))
    )
    (net (code "137") (name "unconnected-(IC9B-PF9-Pad21)") (class "Default")
      (node (ref "IC9") (pin "21") (pinfunction "PF9_21") (pintype "passive"))
    )
    (net (code "138") (name "unconnected-(IC9B-PF10-Pad22)") (class "Default")
      (node (ref "IC9") (pin "22") (pinfunction "PF10_22") (pintype "passive"))
    )
    (net (code "139") (name "unconnected-(IC9B-PF12-Pad50)") (class "Default")
      (node (ref "IC9") (pin "50") (pinfunction "PF12_50") (pintype "passive"))
    )
    (net (code "140") (name "unconnected-(IC9B-PF14-Pad54)") (class "Default")
      (node (ref "IC9") (pin "54") (pinfunction "PF14_54") (pintype "passive"))
    )
    (net (code "141") (name "unconnected-(IC9B-PF15-Pad55)") (class "Default")
      (node (ref "IC9") (pin "55") (pinfunction "PF15_55") (pintype "passive"))
    )
    (net (code "142") (name "unconnected-(IC9B-PG8-Pad93)") (class "Default")
      (node (ref "IC9") (pin "93") (pinfunction "PG8_93") (pintype "passive"))
    )
    (net (code "143") (name "unconnected-(IC9B-PG9-Pad124)") (class "Default")
      (node (ref "IC9") (pin "124") (pinfunction "PG9_124") (pintype "passive"))
    )
    (net (code "144") (name "unconnected-(IC9B-PG10-Pad125)") (class "Default")
      (node (ref "IC9") (pin "125") (pinfunction "PG10_125") (pintype "passive"))
    )
    (net (code "145") (name "unconnected-(IC9B-PG11-Pad126)") (class "Default")
      (node (ref "IC9") (pin "126") (pinfunction "PG11_126") (pintype "passive"))
    )
    (net (code "146") (name "unconnected-(IC9B-PG14-Pad129)") (class "Default")
      (node (ref "IC9") (pin "129") (pinfunction "PG14_129") (pintype "passive"))
    )
    (net (code "147") (name "unconnected-(IC9B-PG15-Pad132)") (class "Default")
      (node (ref "IC9") (pin "132") (pinfunction "PG15_132") (pintype "passive"))
    )
    (net (code "148") (name "unconnected-(IC11-VREF-Pad5)") (class "Default")
      (node (ref "IC11") (pin "5") (pinfunction "VREF_5") (pintype "output"))
    )
    (net (code "149") (name "unconnected-(JP1-Pad7)") (class "Default")
      (node (ref "JP1") (pin "7") (pinfunction "7_7") (pintype "passive"))
    )
  )
)
